# Chov3_cpu.net
KiCad netlist of a schematic drawn in Altium Designer
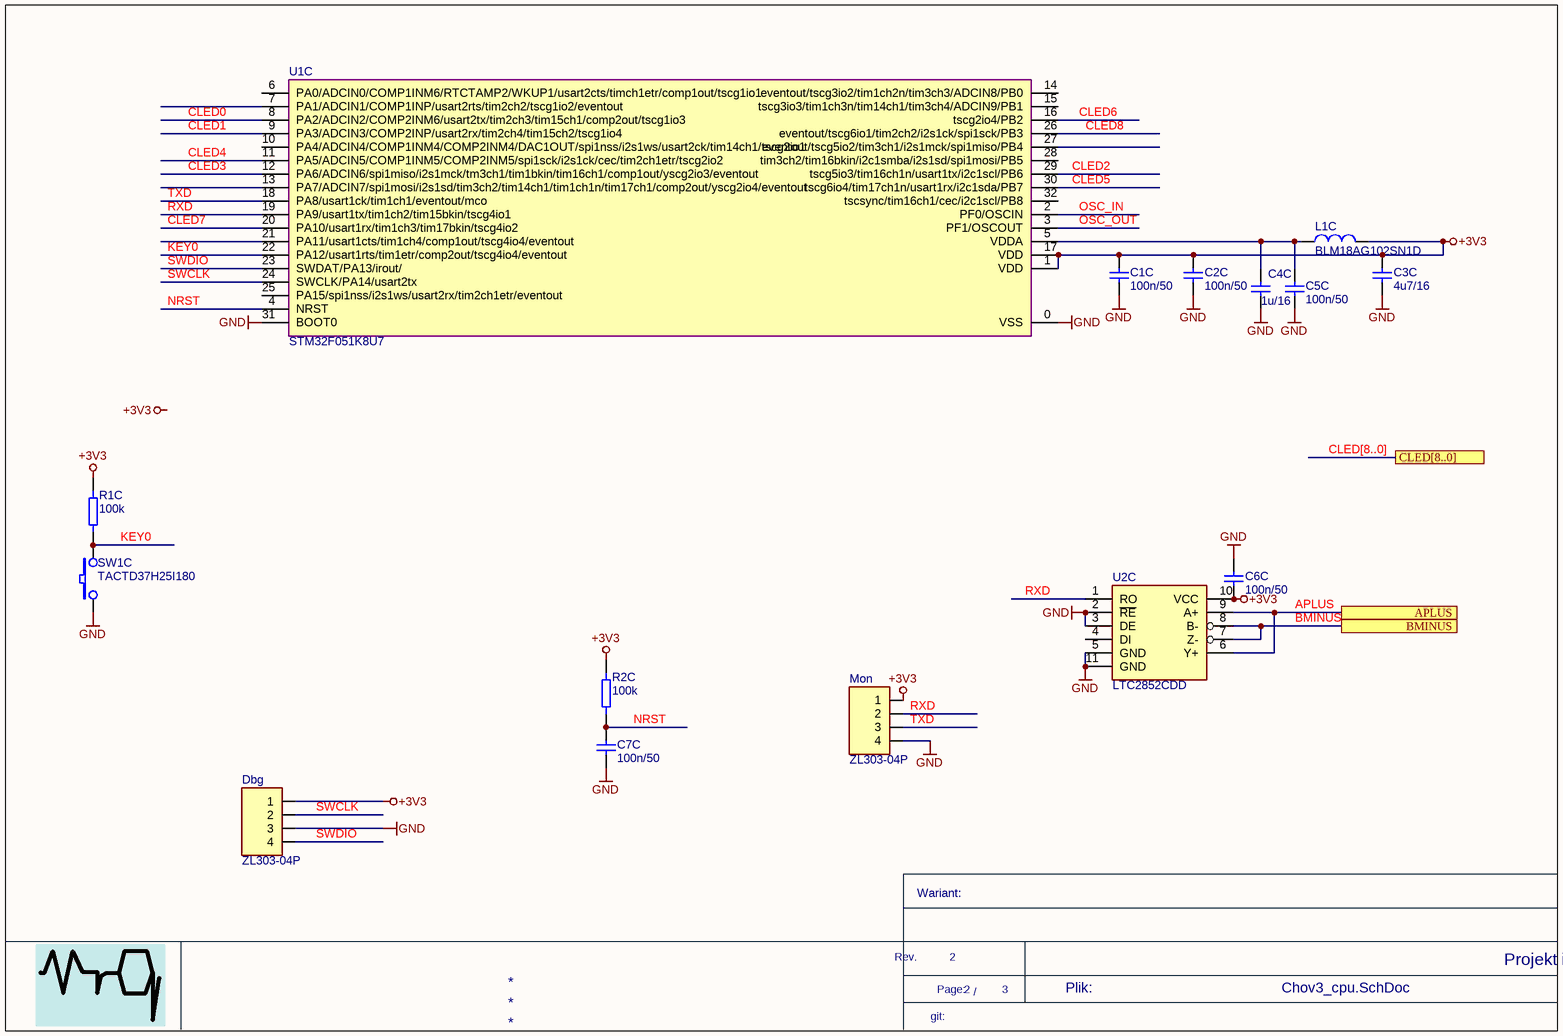
[diagram p0: Chov3_cpu.SchDoc]

(export (version "E")
  (design (tool "Eeschema 10.0.6"))
  (components
    (comp (ref "C1C")
      (value "CL10B104JB8NNNC")
      (footprint "0603-IPC")
      (fields (field (name "OTHERPARAMS") "100n/50") (field (name "TOLERANCE") "10%"))
      (libsource (lib "Parts") (part "C"))
    )
    (comp (ref "C2C")
      (value "CL10B104JB8NNNC")
      (footprint "0603-IPC")
      (fields (field (name "OTHERPARAMS") "100n/50") (field (name "TOLERANCE") "10%"))
      (libsource (lib "Parts") (part "C"))
    )
    (comp (ref "C3C")
      (value "0805YC475KAT2A")
      (footprint "0805")
      (fields (field (name "OTHERPARAMS") "4u7/16") (field (name "TOLERANCE") "10%"))
      (libsource (lib "Parts") (part "C"))
    )
    (comp (ref "C4C")
      (value "CL10B105KO8NNNC")
      (footprint "0603-IPC")
      (fields (field (name "OTHERPARAMS") "1u/16") (field (name "TOLERANCE") "10%"))
      (libsource (lib "Parts") (part "C"))
    )
    (comp (ref "C5C")
      (value "CL10B104JB8NNNC")
      (footprint "0603-IPC")
      (fields (field (name "OTHERPARAMS") "100n/50") (field (name "TOLERANCE") "10%"))
      (libsource (lib "Parts") (part "C"))
    )
    (comp (ref "C6C")
      (value "CL10B104JB8NNNC")
      (footprint "0603-IPC")
      (fields (field (name "OTHERPARAMS") "100n/50") (field (name "TOLERANCE") "10%"))
      (libsource (lib "Parts") (part "C"))
    )
    (comp (ref "C7C")
      (value "CL10B104JB8NNNC")
      (footprint "0603-IPC")
      (fields (field (name "OTHERPARAMS") "100n/50") (field (name "TOLERANCE") "10%"))
      (libsource (lib "Parts") (part "C"))
    )
    (comp (ref "Dbg") (value "ZL303-04P") (footprint "PLMS4S") (libsource (lib "Parts") (part "HEADER4")))
    (comp (ref "L1C")
      (value "BLM18AG102SN1D")
      (footprint "0603-IPC")
      (fields (field (name "OTHERPARAMS") "BLM18AG102SN1D"))
      (libsource (lib "Parts") (part "INDUCTOR"))
    )
    (comp (ref "Mon") (value "ZL303-04P") (footprint "PLMS4S") (libsource (lib "Parts") (part "HEADER4")))
    (comp (ref "R1C")
      (value "0603SAF1003T5E")
      (footprint "0603-IPC")
      (fields (field (name "OTHERPARAMS") "100k") (field (name "TOLERANCE") "1%"))
      (libsource (lib "Parts") (part "R"))
    )
    (comp (ref "R2C")
      (value "0603SAF1003T5E")
      (footprint "0603-IPC")
      (fields (field (name "OTHERPARAMS") "100k") (field (name "TOLERANCE") "1%"))
      (libsource (lib "Parts") (part "R"))
    )
    (comp (ref "SW1C")
      (value "TACTD37H25I180")
      (footprint "TACTD37H25I180")
      (libsource (lib "Parts") (part "DTSM31NB"))
    )
    (comp (ref "U1C")
      (value "STM32F051K8U7")
      (footprint "UFQFPN32_5x5")
      (libsource (lib "Parts") (part "STM32F051K8U7"))
    )
    (comp (ref "U2C")
      (value "LTC2852CDD")
      (footprint "MO-229WEED-2")
      (libsource (lib "Parts") (part "LTC2852CDD"))
    )
  )
  (nets
    (net (code "1") (name "+3V3") (class "Default")
      (node (ref "C1C") (pin "1") (pinfunction "1_1") (pintype "passive"))
      (node (ref "C2C") (pin "1") (pinfunction "1_1") (pintype "passive"))
      (node (ref "C3C") (pin "1") (pinfunction "1_1") (pintype "passive"))
      (node (ref "C6C") (pin "1") (pinfunction "1_1") (pintype "passive"))
      (node (ref "Dbg") (pin "1") (pinfunction "1_1") (pintype "passive"))
      (node (ref "L1C") (pin "2") (pinfunction "2_2") (pintype "passive"))
      (node (ref "Mon") (pin "1") (pinfunction "1_1") (pintype "passive"))
      (node (ref "R1C") (pin "1") (pinfunction "1_1") (pintype "passive"))
      (node (ref "R2C") (pin "1") (pinfunction "1_1") (pintype "passive"))
      (node (ref "U1C") (pin "1") (pinfunction "VDD_1") (pintype "passive"))
      (node (ref "U1C") (pin "17") (pinfunction "VDD_17") (pintype "passive"))
      (node (ref "U2C") (pin "10") (pinfunction "VCC_10") (pintype "passive"))
    )
    (net (code "2") (name "/APLUS") (class "Default")
      (node (ref "U2C") (pin "6") (pinfunction "Y+_6") (pintype "passive"))
      (node (ref "U2C") (pin "9") (pinfunction "A+_9") (pintype "passive"))
    )
    (net (code "3") (name "/BMINUS") (class "Default")
      (node (ref "U2C") (pin "7") (pinfunction "Z-_7") (pintype "passive"))
      (node (ref "U2C") (pin "8") (pinfunction "B-_8") (pintype "passive"))
    )
    (net (code "4") (name "/CLED0") (class "Default")
      (node (ref "U1C") (pin "8") (pinfunction "PA2/ADCIN2/COMP2INM6/usart2tx/tim2ch3/tim15ch1/comp2out/tscg1io3_8") (pintype "passive"))
    )
    (net (code "5") (name "/CLED1") (class "Default")
      (node (ref "U1C") (pin "9") (pinfunction "PA3/ADCIN3/COMP2INP/usart2rx/tim2ch4/tim15ch2/tscg1io4_9") (pintype "passive"))
    )
    (net (code "6") (name "/CLED2") (class "Default")
      (node (ref "U1C") (pin "29") (pinfunction "tscg5io3/tim16ch1n/usart1tx/i2c1scl/PB6_29") (pintype "passive"))
    )
    (net (code "7") (name "/CLED3") (class "Default")
      (node (ref "U1C") (pin "12") (pinfunction "PA6/ADCIN6/spi1miso/i2s1mck/tm3ch1/tim1bkin/tim16ch1/comp1out/yscg2io3/eventout_12") (pintype "passive"))
    )
    (net (code "8") (name "/CLED4") (class "Default")
      (node (ref "U1C") (pin "11") (pinfunction "PA5/ADCIN5/COMP1INM5/COMP2INM5/spi1sck/i2s1ck/cec/tim2ch1etr/tscg2io2_11") (pintype "passive"))
    )
    (net (code "9") (name "/CLED5") (class "Default")
      (node (ref "U1C") (pin "30") (pinfunction "tscg6io4/tim17ch1n/usart1rx/i2c1sda/PB7_30") (pintype "passive"))
    )
    (net (code "10") (name "/CLED6") (class "Default")
      (node (ref "U1C") (pin "16") (pinfunction "tscg2io4/PB2_16") (pintype "passive"))
    )
    (net (code "11") (name "/CLED7") (class "Default")
      (node (ref "U1C") (pin "20") (pinfunction "PA10/usart1rx/tim1ch3/tim17bkin/tscg4io2_20") (pintype "passive"))
    )
    (net (code "12") (name "/CLED8") (class "Default")
      (node (ref "U1C") (pin "26") (pinfunction "eventout/tscg6io1/tim2ch2/i2s1ck/spi1sck/PB3_26") (pintype "passive"))
    )
    (net (code "14") (name "/KEY0") (class "Default")
      (node (ref "R1C") (pin "2") (pinfunction "2_2") (pintype "passive"))
      (node (ref "SW1C") (pin "2") (pinfunction "2_2") (pintype "passive"))
      (node (ref "U1C") (pin "22") (pinfunction "PA12/usart1rts/tim1etr/comp2out/tscg4io4/eventout_22") (pintype "passive"))
    )
    (net (code "15") (name "/NRST") (class "Default")
      (node (ref "C7C") (pin "1") (pinfunction "1_1") (pintype "passive"))
      (node (ref "R2C") (pin "2") (pinfunction "2_2") (pintype "passive"))
      (node (ref "U1C") (pin "4") (pinfunction "NRST_4") (pintype "passive"))
    )
    (net (code "16") (name "/OSC_IN") (class "Default")
      (node (ref "U1C") (pin "2") (pinfunction "PF0/OSCIN_2") (pintype "passive"))
    )
    (net (code "17") (name "/OSC_OUT") (class "Default")
      (node (ref "U1C") (pin "3") (pinfunction "PF1/OSCOUT_3") (pintype "passive"))
    )
    (net (code "18") (name "/RXD") (class "Default")
      (node (ref "Mon") (pin "2") (pinfunction "2_2") (pintype "passive"))
      (node (ref "U1C") (pin "19") (pinfunction "PA9/usart1tx/tim1ch2/tim15bkin/tscg4io1_19") (pintype "passive"))
      (node (ref "U2C") (pin "1") (pinfunction "RO_1") (pintype "passive"))
    )
    (net (code "19") (name "/SWCLK") (class "Default")
      (node (ref "Dbg") (pin "2") (pinfunction "2_2") (pintype "passive"))
      (node (ref "U1C") (pin "24") (pinfunction "SWCLK/PA14/usart2tx_24") (pintype "passive"))
    )
    (net (code "20") (name "/SWDIO") (class "Default")
      (node (ref "Dbg") (pin "4") (pinfunction "4_4") (pintype "passive"))
      (node (ref "U1C") (pin "23") (pinfunction "SWDAT/PA13/irout/_23") (pintype "passive"))
    )
    (net (code "21") (name "/TXD") (class "Default")
      (node (ref "Mon") (pin "3") (pinfunction "3_3") (pintype "passive"))
      (node (ref "U1C") (pin "18") (pinfunction "PA8/usart1ck/tim1ch1/eventout/mco_18") (pintype "passive"))
    )
    (net (code "22") (name "GND") (class "Default")
      (node (ref "C1C") (pin "2") (pinfunction "2_2") (pintype "passive"))
      (node (ref "C2C") (pin "2") (pinfunction "2_2") (pintype "passive"))
      (node (ref "C3C") (pin "2") (pinfunction "2_2") (pintype "passive"))
      (node (ref "C4C") (pin "2") (pinfunction "2_2") (pintype "passive"))
      (node (ref "C5C") (pin "2") (pinfunction "2_2") (pintype "passive"))
      (node (ref "C6C") (pin "2") (pinfunction "2_2") (pintype "passive"))
      (node (ref "C7C") (pin "2") (pinfunction "2_2") (pintype "passive"))
      (node (ref "Dbg") (pin "3") (pinfunction "3_3") (pintype "passive"))
      (node (ref "Mon") (pin "4") (pinfunction "4_4") (pintype "passive"))
      (node (ref "SW1C") (pin "1") (pinfunction "1_1") (pintype "passive"))
      (node (ref "U1C") (pin "0") (pinfunction "VSS_0") (pintype "passive"))
      (node (ref "U1C") (pin "31") (pinfunction "BOOT0_31") (pintype "passive"))
      (node (ref "U2C") (pin "11") (pinfunction "GND_11") (pintype "passive"))
      (node (ref "U2C") (pin "2") (pinfunction "~{RE}_2") (pintype "passive"))
      (node (ref "U2C") (pin "3") (pinfunction "DE_3") (pintype "passive"))
      (node (ref "U2C") (pin "5") (pinfunction "GND_5") (pintype "passive"))
    )
    (net (code "23") (name "Net-(U1C-VDDA)") (class "Default")
      (node (ref "C4C") (pin "1") (pinfunction "1_1") (pintype "passive"))
      (node (ref "C5C") (pin "1") (pinfunction "1_1") (pintype "passive"))
      (node (ref "L1C") (pin "1") (pinfunction "1_1") (pintype "passive"))
      (node (ref "U1C") (pin "5") (pinfunction "VDDA_5") (pintype "passive"))
    )
    (net (code "24") (name "unconnected-(U1C-PA0{slash}ADCIN0{slash}COMP1INM6{slash}RTCTAMP2{slash}WKUP1{slash}usart2cts{slash}timch1etr{slash}comp1out{slash}tscg1io1-Pad6)") (class "Default")
      (node (ref "U1C") (pin "6") (pinfunction "PA0/ADCIN0/COMP1INM6/RTCTAMP2/WKUP1/usart2cts/timch1etr/comp1out/tscg1io1_6") (pintype "passive"))
    )
    (net (code "25") (name "unconnected-(U1C-PA1{slash}ADCIN1{slash}COMP1INP{slash}usart2rts{slash}tim2ch2{slash}tscg1io2{slash}eventout-Pad7)") (class "Default")
      (node (ref "U1C") (pin "7") (pinfunction "PA1/ADCIN1/COMP1INP/usart2rts/tim2ch2/tscg1io2/eventout_7") (pintype "passive"))
    )
    (net (code "26") (name "unconnected-(U1C-PA4{slash}ADCIN4{slash}COMP1INM4{slash}COMP2INM4{slash}DAC1OUT{slash}spi1nss{slash}i2s1ws{slash}usart2ck{slash}tim14ch1{slash}tscg2io1-Pad10)") (class "Default")
      (node (ref "U1C") (pin "10") (pinfunction "PA4/ADCIN4/COMP1INM4/COMP2INM4/DAC1OUT/spi1nss/i2s1ws/usart2ck/tim14ch1/tscg2io1_10") (pintype "passive"))
    )
    (net (code "27") (name "unconnected-(U1C-PA7{slash}ADCIN7{slash}spi1mosi{slash}i2s1sd{slash}tim3ch2{slash}tim14ch1{slash}tim1ch1n{slash}tim17ch1{slash}comp2out{slash}yscg2io4{slash}eventout-Pad13)") (class "Default")
      (node (ref "U1C") (pin "13") (pinfunction "PA7/ADCIN7/spi1mosi/i2s1sd/tim3ch2/tim14ch1/tim1ch1n/tim17ch1/comp2out/yscg2io4/eventout_13") (pintype "passive"))
    )
    (net (code "28") (name "unconnected-(U1C-PA11{slash}usart1cts{slash}tim1ch4{slash}comp1out{slash}tscg4io4{slash}eventout-Pad21)") (class "Default")
      (node (ref "U1C") (pin "21") (pinfunction "PA11/usart1cts/tim1ch4/comp1out/tscg4io4/eventout_21") (pintype "passive"))
    )
    (net (code "29") (name "unconnected-(U1C-PA15{slash}spi1nss{slash}i2s1ws{slash}usart2rx{slash}tim2ch1etr{slash}eventout-Pad25)") (class "Default")
      (node (ref "U1C") (pin "25") (pinfunction "PA15/spi1nss/i2s1ws/usart2rx/tim2ch1etr/eventout_25") (pintype "passive"))
    )
    (net (code "30") (name "unconnected-(U1C-eventout{slash}tscg3io2{slash}tim1ch2n{slash}tim3ch3{slash}ADCIN8{slash}PB0-Pad14)") (class "Default")
      (node (ref "U1C") (pin "14") (pinfunction "eventout/tscg3io2/tim1ch2n/tim3ch3/ADCIN8/PB0_14") (pintype "passive"))
    )
    (net (code "31") (name "unconnected-(U1C-eventout{slash}tscg5io2{slash}tim3ch1{slash}i2s1mck{slash}spi1miso{slash}PB4-Pad27)") (class "Default")
      (node (ref "U1C") (pin "27") (pinfunction "eventout/tscg5io2/tim3ch1/i2s1mck/spi1miso/PB4_27") (pintype "passive"))
    )
    (net (code "32") (name "unconnected-(U1C-tim3ch2{slash}tim16bkin{slash}i2c1smba{slash}i2s1sd{slash}spi1mosi{slash}PB5-Pad28)") (class "Default")
      (node (ref "U1C") (pin "28") (pinfunction "tim3ch2/tim16bkin/i2c1smba/i2s1sd/spi1mosi/PB5_28") (pintype "passive"))
    )
    (net (code "33") (name "unconnected-(U1C-tscg3io3{slash}tim1ch3n{slash}tim14ch1{slash}tim3ch4{slash}ADCIN9{slash}PB1-Pad15)") (class "Default")
      (node (ref "U1C") (pin "15") (pinfunction "tscg3io3/tim1ch3n/tim14ch1/tim3ch4/ADCIN9/PB1_15") (pintype "passive"))
    )
    (net (code "34") (name "unconnected-(U1C-tscsync{slash}tim16ch1{slash}cec{slash}i2c1scl{slash}PB8-Pad32)") (class "Default")
      (node (ref "U1C") (pin "32") (pinfunction "tscsync/tim16ch1/cec/i2c1scl/PB8_32") (pintype "passive"))
    )
    (net (code "35") (name "unconnected-(U2C-DI-Pad4)") (class "Default")
      (node (ref "U2C") (pin "4") (pinfunction "DI_4") (pintype "passive"))
    )
  )
)
